# PLD_Connectors_Piggyback.net
KiCad netlist of a schematic drawn in Altium Designer
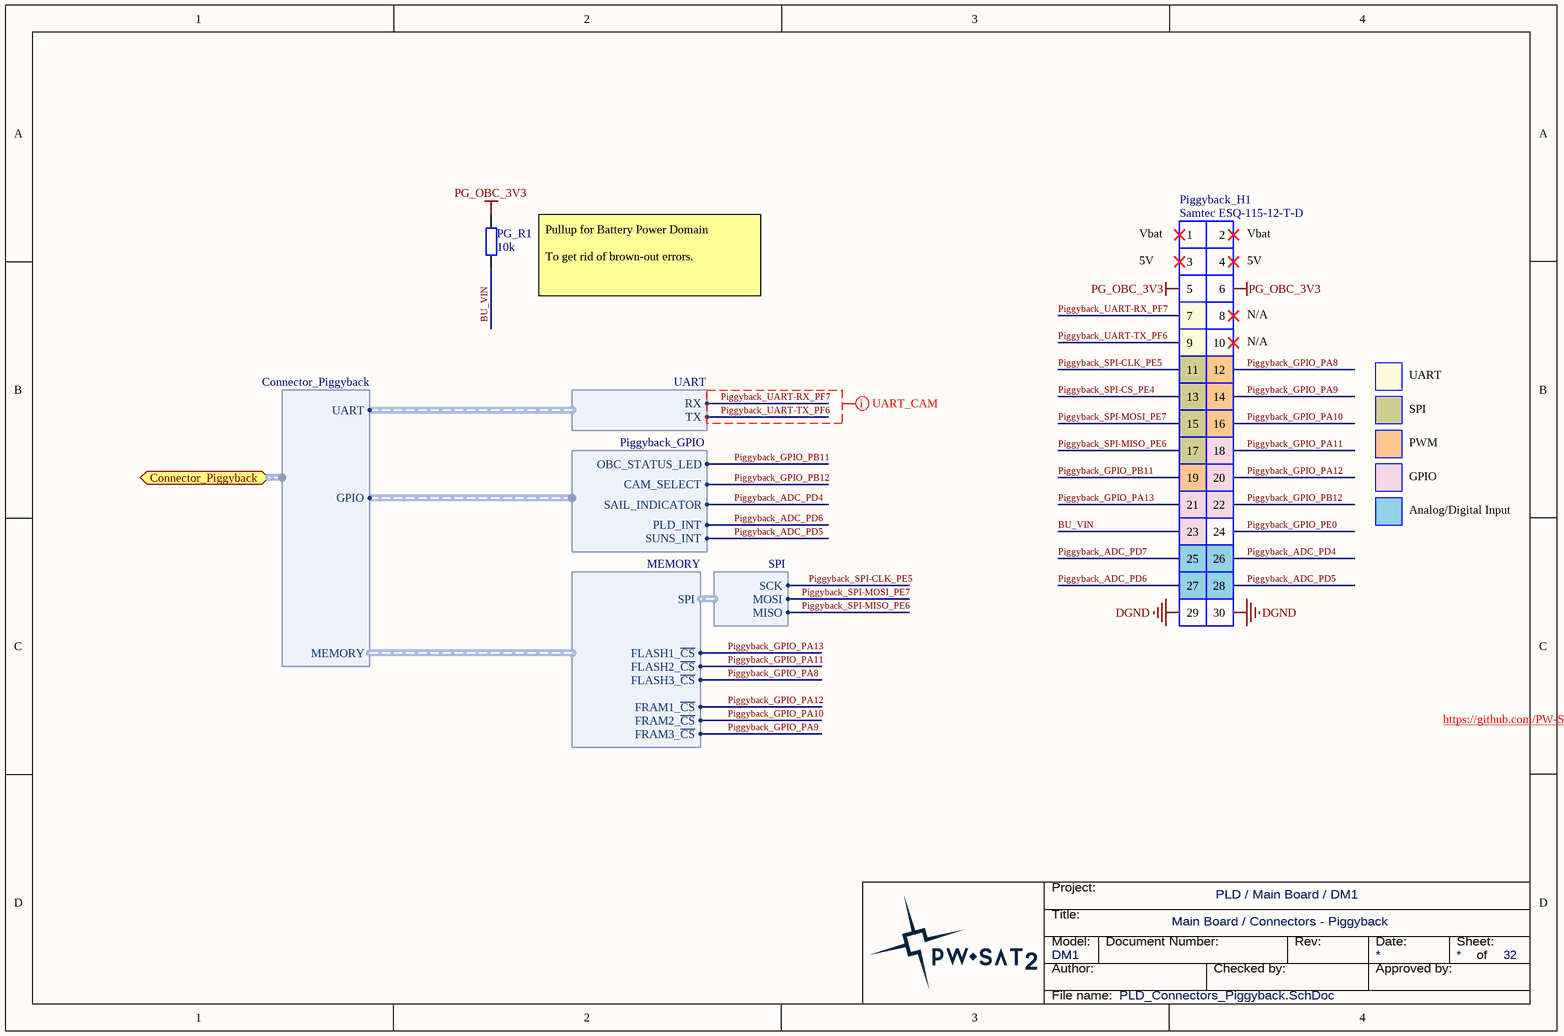
[diagram p0: PLD_Connectors_Piggyback.SchDoc]

(export (version "E")
  (design (tool "Eeschema 10.0.6"))
  (components
    (comp (ref "PG_R1")
      (value "10k")
      (footprint "SMD_Resistor_0603")
      (libsource (lib "resistors") (part "Res"))
    )
    (comp (ref "Piggyback_H1")
      (value "Samtec ESQ-115-12-T-D")
      (footprint "Samtec_ESQ-115-12-T-D")
      (description "Samtec ESQ Series Header , 2.54mm pitch, 2x15pin. PC-104 Stack Connector.")
      (libsource (lib "connectors_printed-circuit-board") (part "Samtec_ESQ-115-xx-x-D"))
    )
  )
  (nets
    (net (code "5") (name "/BU_VIN") (class "Default")
      (node (ref "PG_R1") (pin "1") (pinfunction "1_1") (pintype "passive"))
      (node (ref "Piggyback_H1") (pin "23") (pinfunction "23_23") (pintype "passive"))
    )
    (net (code "7") (name "/Piggyback_ADC_PD4") (class "Default")
      (node (ref "Piggyback_H1") (pin "26") (pinfunction "26_26") (pintype "passive"))
    )
    (net (code "8") (name "/Piggyback_ADC_PD5") (class "Default")
      (node (ref "Piggyback_H1") (pin "28") (pinfunction "28_28") (pintype "passive"))
    )
    (net (code "9") (name "/Piggyback_ADC_PD6") (class "Default")
      (node (ref "Piggyback_H1") (pin "27") (pinfunction "27_27") (pintype "passive"))
    )
    (net (code "10") (name "/Piggyback_ADC_PD7") (class "Default")
      (node (ref "Piggyback_H1") (pin "25") (pinfunction "25_25") (pintype "passive"))
    )
    (net (code "11") (name "/Piggyback_GPIO_PA8") (class "Default")
      (node (ref "Piggyback_H1") (pin "12") (pinfunction "12_12") (pintype "passive"))
    )
    (net (code "12") (name "/Piggyback_GPIO_PA9") (class "Default")
      (node (ref "Piggyback_H1") (pin "14") (pinfunction "14_14") (pintype "passive"))
    )
    (net (code "13") (name "/Piggyback_GPIO_PA10") (class "Default")
      (node (ref "Piggyback_H1") (pin "16") (pinfunction "16_16") (pintype "passive"))
    )
    (net (code "14") (name "/Piggyback_GPIO_PA11") (class "Default")
      (node (ref "Piggyback_H1") (pin "18") (pinfunction "18_18") (pintype "passive"))
    )
    (net (code "15") (name "/Piggyback_GPIO_PA12") (class "Default")
      (node (ref "Piggyback_H1") (pin "20") (pinfunction "20_20") (pintype "passive"))
    )
    (net (code "16") (name "/Piggyback_GPIO_PA13") (class "Default")
      (node (ref "Piggyback_H1") (pin "21") (pinfunction "21_21") (pintype "passive"))
    )
    (net (code "17") (name "/Piggyback_GPIO_PB11") (class "Default")
      (node (ref "Piggyback_H1") (pin "19") (pinfunction "19_19") (pintype "passive"))
    )
    (net (code "18") (name "/Piggyback_GPIO_PB12") (class "Default")
      (node (ref "Piggyback_H1") (pin "22") (pinfunction "22_22") (pintype "passive"))
    )
    (net (code "19") (name "/Piggyback_GPIO_PE0") (class "Default")
      (node (ref "Piggyback_H1") (pin "24") (pinfunction "24_24") (pintype "passive"))
    )
    (net (code "20") (name "/Piggyback_SPI-CLK_PE5") (class "Default")
      (node (ref "Piggyback_H1") (pin "11") (pinfunction "11_11") (pintype "passive"))
    )
    (net (code "21") (name "/Piggyback_SPI-CS_PE4") (class "Default")
      (node (ref "Piggyback_H1") (pin "13") (pinfunction "13_13") (pintype "passive"))
    )
    (net (code "22") (name "/Piggyback_SPI-MISO_PE6") (class "Default")
      (node (ref "Piggyback_H1") (pin "17") (pinfunction "17_17") (pintype "passive"))
    )
    (net (code "23") (name "/Piggyback_SPI-MOSI_PE7") (class "Default")
      (node (ref "Piggyback_H1") (pin "15") (pinfunction "15_15") (pintype "passive"))
    )
    (net (code "24") (name "/Piggyback_UART-RX_PF7") (class "Default")
      (node (ref "Piggyback_H1") (pin "7") (pinfunction "7_7") (pintype "passive"))
    )
    (net (code "25") (name "/Piggyback_UART-TX_PF6") (class "Default")
      (node (ref "Piggyback_H1") (pin "9") (pinfunction "9_9") (pintype "passive"))
    )
    (net (code "29") (name "DGND") (class "Default")
      (node (ref "Piggyback_H1") (pin "29") (pinfunction "29_29") (pintype "passive"))
      (node (ref "Piggyback_H1") (pin "30") (pinfunction "30_30") (pintype "passive"))
    )
    (net (code "30") (name "PG_OBC_3V3") (class "Default")
      (node (ref "PG_R1") (pin "2") (pinfunction "2_2") (pintype "passive"))
      (node (ref "Piggyback_H1") (pin "5") (pinfunction "5_5") (pintype "passive"))
      (node (ref "Piggyback_H1") (pin "6") (pinfunction "6_6") (pintype "passive"))
    )
    (net (code "31") (name "unconnected-(Piggyback_H1-Pad1)") (class "Default")
      (node (ref "Piggyback_H1") (pin "1") (pinfunction "1_1") (pintype "passive+no_connect"))
    )
    (net (code "32") (name "unconnected-(Piggyback_H1-Pad2)") (class "Default")
      (node (ref "Piggyback_H1") (pin "2") (pinfunction "2_2") (pintype "passive+no_connect"))
    )
    (net (code "33") (name "unconnected-(Piggyback_H1-Pad3)") (class "Default")
      (node (ref "Piggyback_H1") (pin "3") (pinfunction "3_3") (pintype "passive+no_connect"))
    )
    (net (code "34") (name "unconnected-(Piggyback_H1-Pad4)") (class "Default")
      (node (ref "Piggyback_H1") (pin "4") (pinfunction "4_4") (pintype "passive+no_connect"))
    )
    (net (code "35") (name "unconnected-(Piggyback_H1-Pad8)") (class "Default")
      (node (ref "Piggyback_H1") (pin "8") (pinfunction "8_8") (pintype "passive+no_connect"))
    )
    (net (code "36") (name "unconnected-(Piggyback_H1-Pad10)") (class "Default")
      (node (ref "Piggyback_H1") (pin "10") (pinfunction "10_10") (pintype "passive+no_connect"))
    )
  )
)
